# HLK-AX3000-KIT-RJ45.net
KiCad netlist of a schematic drawn in Altium Designer
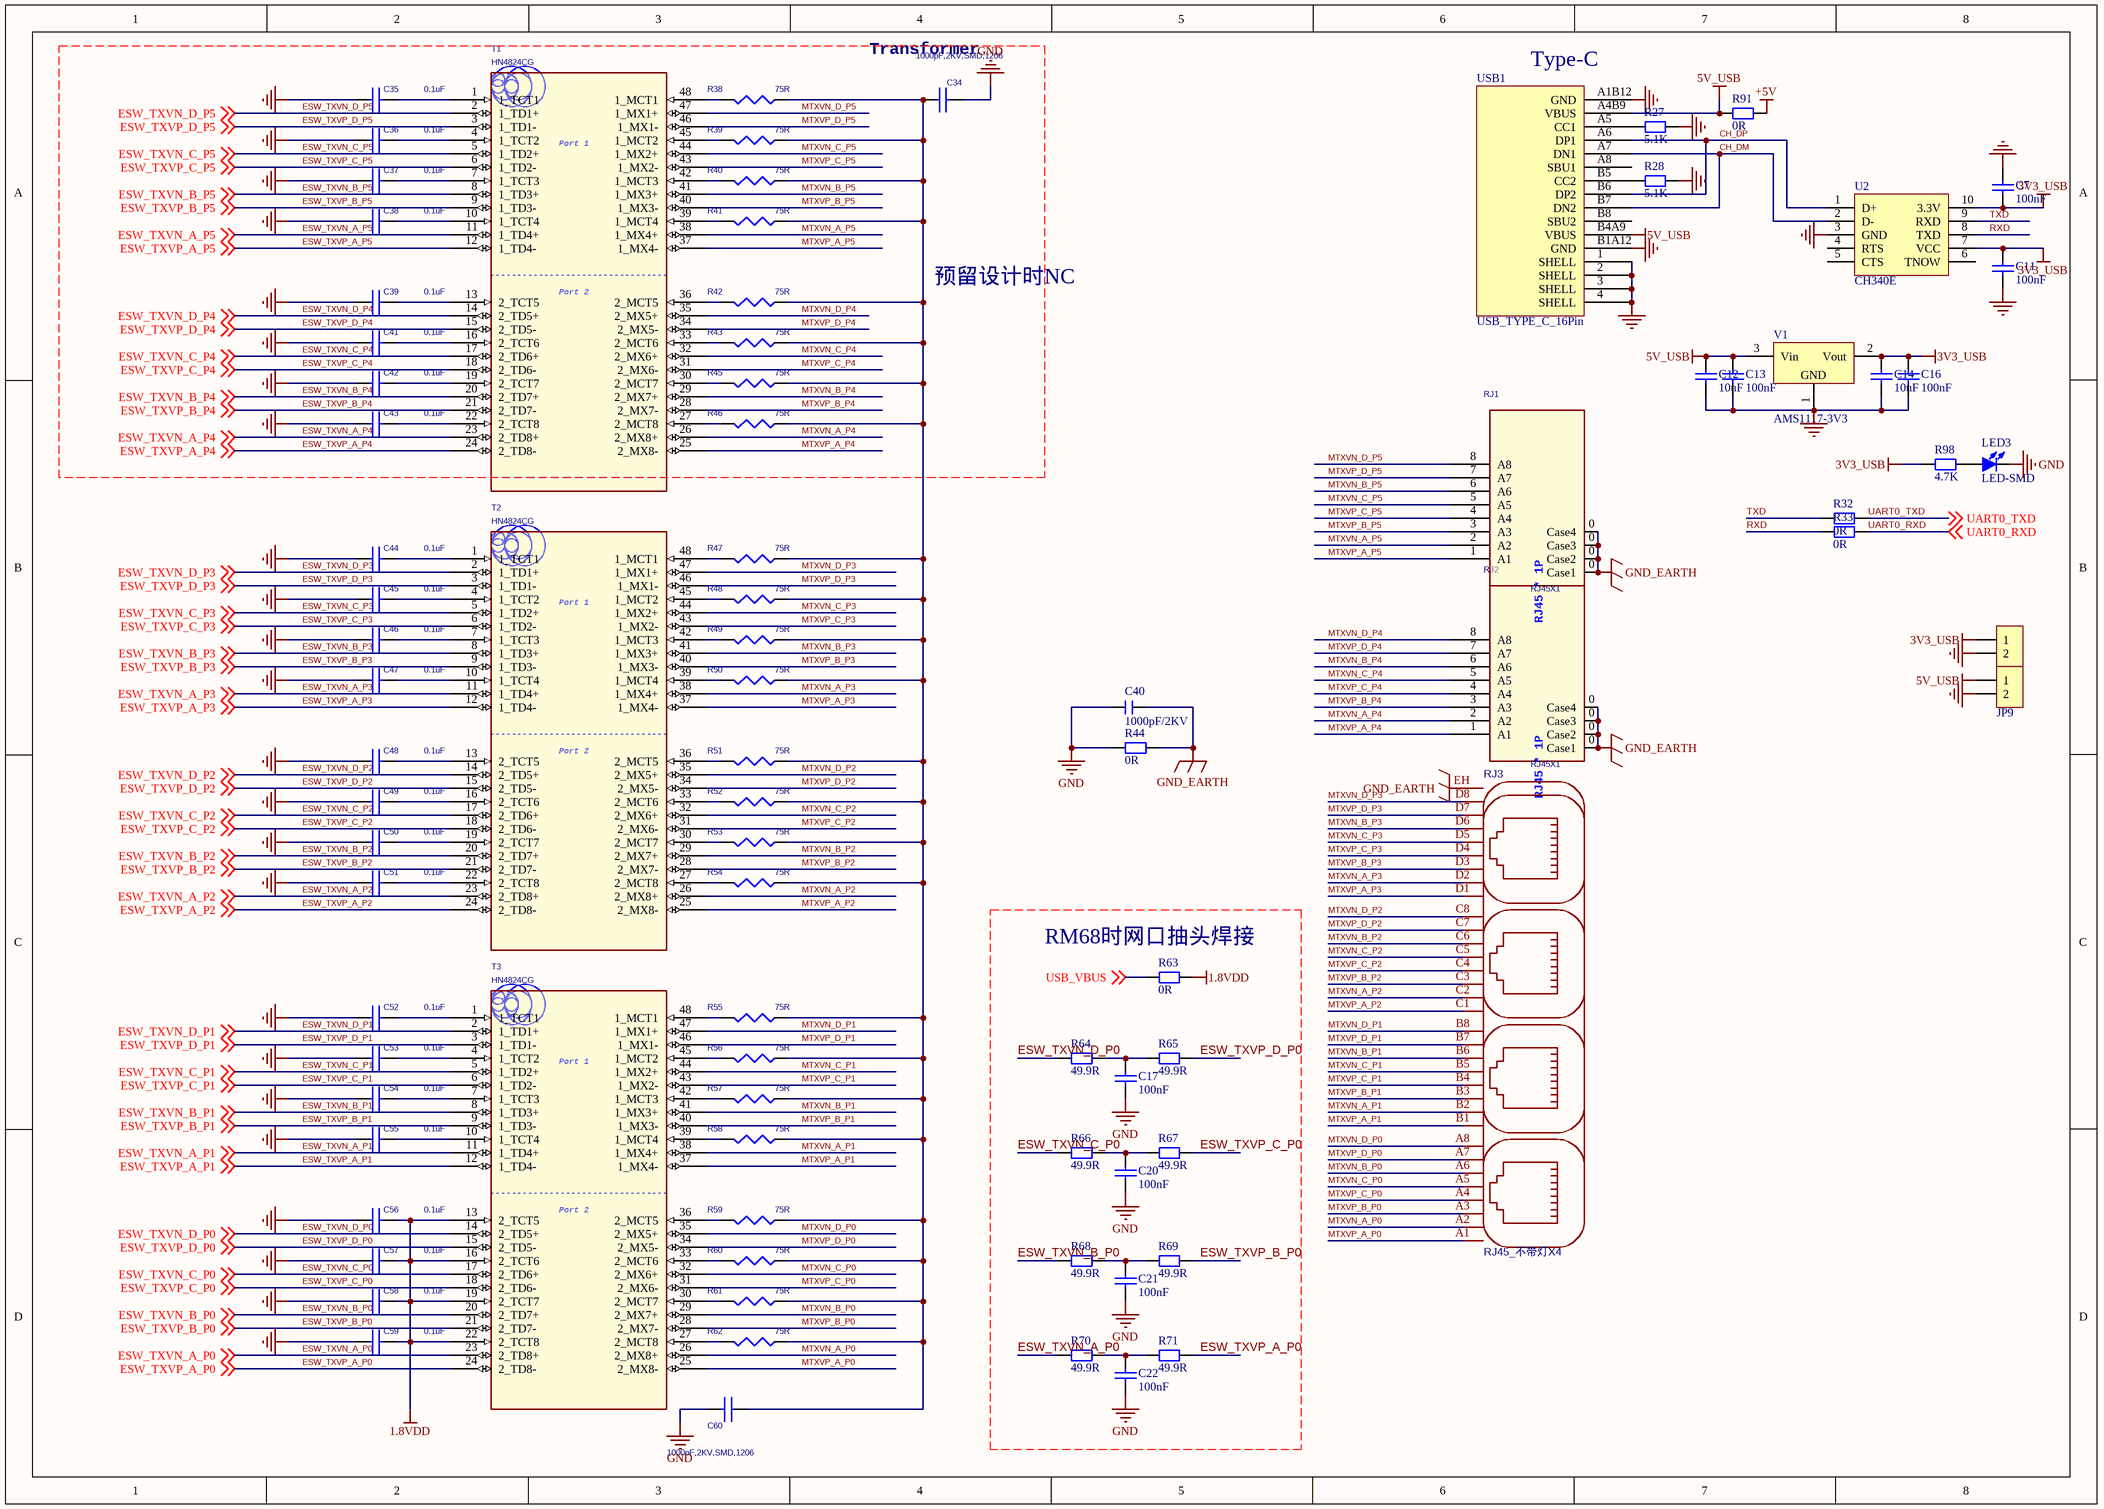
[diagram p0: HLK-AX3000-KIT-RJ45.SchDoc]

(export (version "E")
  (design (tool "Eeschema 10.0.6"))
  (components
    (comp (ref "C7")
      (value "100nF")
      (footprint "C 0402_L")
      (description "Capacitor")
      (libsource (lib "LORATEMPSENSOR_V0.02") (part "Cap"))
    )
    (comp (ref "C11")
      (value "100nF")
      (footprint "C 0402_L")
      (description "Capacitor")
      (libsource (lib "LORATEMPSENSOR_V0.02") (part "Cap"))
    )
    (comp (ref "C12")
      (value "10uF")
      (footprint "C 0603_L")
      (description "Capacitor")
      (fields
        (field (name "MANUFACTURER") "Generic Components")
        (field (name "PUBLISHER") "Altium Hobart Technology Centre")
      )
      (libsource (lib "*") (part "Cap"))
    )
    (comp (ref "C13")
      (value "100nF")
      (footprint "C 0402_L")
      (description "Capacitor")
      (libsource (lib "LORATEMPSENSOR_V0.02") (part "Cap"))
    )
    (comp (ref "C14")
      (value "10uF")
      (footprint "C 0603_L")
      (description "Capacitor")
      (fields
        (field (name "MANUFACTURER") "Generic Components")
        (field (name "PUBLISHER") "Altium Hobart Technology Centre")
      )
      (libsource (lib "*") (part "Cap"))
    )
    (comp (ref "C16")
      (value "100nF")
      (footprint "C 0402_L")
      (description "Capacitor")
      (libsource (lib "LORATEMPSENSOR_V0.02") (part "Cap"))
    )
    (comp (ref "C17")
      (value "100nF")
      (footprint "C 0402_L")
      (description "Capacitor")
      (libsource (lib "LORATEMPSENSOR_V0.02") (part "Cap"))
    )
    (comp (ref "C20")
      (value "100nF")
      (footprint "C 0402_L")
      (description "Capacitor")
      (libsource (lib "LORATEMPSENSOR_V0.02") (part "Cap"))
    )
    (comp (ref "C21")
      (value "100nF")
      (footprint "C 0402_L")
      (description "Capacitor")
      (libsource (lib "LORATEMPSENSOR_V0.02") (part "Cap"))
    )
    (comp (ref "C22")
      (value "100nF")
      (footprint "C 0402_L")
      (description "Capacitor")
      (libsource (lib "LORATEMPSENSOR_V0.02") (part "Cap"))
    )
    (comp (ref "C34")
      (value "1000pF,2KV,SMD,1206")
      (footprint "C 1206_L")
      (description "Cap, HighVolt, SMD 1206, 2KV")
      (fields (field (name "MANUFACTURER") "Arcotromics") (field (name "BY") "Ralink"))
      (libsource (lib "*") (part "CAP NP_Dup1"))
    )
    (comp (ref "C35")
      (value "0.1uF")
      (footprint "C 0402_L")
      (description "Cap, MLCC, 0402, Y5V, 16V")
      (fields
        (field (name "MANUFACTURER") "地穝")
        (field (name "PART NUMBER") "100-110-03400")
        (field (name "BY") "Ralink")
      )
      (libsource (lib "*") (part "0.1UF/25V_+80%-20%_CC_S0603"))
    )
    (comp (ref "C36")
      (value "0.1uF")
      (footprint "C 0402_L")
      (description "Cap, MLCC, 0402, Y5V, 16V")
      (fields
        (field (name "MANUFACTURER") "地穝")
        (field (name "PART NUMBER") "100-110-03400")
        (field (name "BY") "Ralink")
      )
      (libsource (lib "*") (part "0.1UF/25V_+80%-20%_CC_S0603"))
    )
    (comp (ref "C37")
      (value "0.1uF")
      (footprint "C 0402_L")
      (description "Cap, MLCC, 0402, Y5V, 16V")
      (fields
        (field (name "MANUFACTURER") "地穝")
        (field (name "PART NUMBER") "100-110-03400")
        (field (name "BY") "Ralink")
      )
      (libsource (lib "*") (part "0.1UF/25V_+80%-20%_CC_S0603"))
    )
    (comp (ref "C38")
      (value "0.1uF")
      (footprint "C 0402_L")
      (description "Cap, MLCC, 0402, Y5V, 16V")
      (fields
        (field (name "MANUFACTURER") "地穝")
        (field (name "PART NUMBER") "100-110-03400")
        (field (name "BY") "Ralink")
      )
      (libsource (lib "*") (part "0.1UF/25V_+80%-20%_CC_S0603"))
    )
    (comp (ref "C39")
      (value "0.1uF")
      (footprint "C 0402_L")
      (description "Cap, MLCC, 0402, Y5V, 16V")
      (fields
        (field (name "MANUFACTURER") "地穝")
        (field (name "PART NUMBER") "100-110-03400")
        (field (name "BY") "Ralink")
      )
      (libsource (lib "*") (part "0.1UF/25V_+80%-20%_CC_S0603"))
    )
    (comp (ref "C40")
      (value "1000pF/2KV")
      (footprint "C 1206_L")
      (description "无极性贴片电容")
      (fields (field (name "版权归属") "源创客"))
      (libsource (lib "3.1   - 电阻-电容-电感") (part "C"))
    )
    (comp (ref "C41")
      (value "0.1uF")
      (footprint "C 0402_L")
      (description "Cap, MLCC, 0402, Y5V, 16V")
      (fields
        (field (name "MANUFACTURER") "地穝")
        (field (name "PART NUMBER") "100-110-03400")
        (field (name "BY") "Ralink")
      )
      (libsource (lib "*") (part "0.1UF/25V_+80%-20%_CC_S0603"))
    )
    (comp (ref "C42")
      (value "0.1uF")
      (footprint "C 0402_L")
      (description "Cap, MLCC, 0402, Y5V, 16V")
      (fields
        (field (name "MANUFACTURER") "地穝")
        (field (name "PART NUMBER") "100-110-03400")
        (field (name "BY") "Ralink")
      )
      (libsource (lib "*") (part "0.1UF/25V_+80%-20%_CC_S0603"))
    )
    (comp (ref "C43")
      (value "0.1uF")
      (footprint "C 0402_L")
      (description "Cap, MLCC, 0402, Y5V, 16V")
      (fields
        (field (name "MANUFACTURER") "地穝")
        (field (name "PART NUMBER") "100-110-03400")
        (field (name "BY") "Ralink")
      )
      (libsource (lib "*") (part "0.1UF/25V_+80%-20%_CC_S0603"))
    )
    (comp (ref "C44")
      (value "0.1uF")
      (footprint "C 0402_L")
      (description "Cap, MLCC, 0402, Y5V, 16V")
      (fields
        (field (name "PART NUMBER") "100-110-03400")
        (field (name "MANUFACTURER") "地穝")
        (field (name "BY") "Ralink")
      )
      (libsource (lib "*") (part "0.1UF/25V_+80%-20%_CC_S0603"))
    )
    (comp (ref "C45")
      (value "0.1uF")
      (footprint "C 0402_L")
      (description "Cap, MLCC, 0402, Y5V, 16V")
      (fields
        (field (name "PART NUMBER") "100-110-03400")
        (field (name "MANUFACTURER") "地穝")
        (field (name "BY") "Ralink")
      )
      (libsource (lib "*") (part "0.1UF/25V_+80%-20%_CC_S0603"))
    )
    (comp (ref "C46")
      (value "0.1uF")
      (footprint "C 0402_L")
      (description "Cap, MLCC, 0402, Y5V, 16V")
      (fields
        (field (name "PART NUMBER") "100-110-03400")
        (field (name "MANUFACTURER") "地穝")
        (field (name "BY") "Ralink")
      )
      (libsource (lib "*") (part "0.1UF/25V_+80%-20%_CC_S0603"))
    )
    (comp (ref "C47")
      (value "0.1uF")
      (footprint "C 0402_L")
      (description "Cap, MLCC, 0402, Y5V, 16V")
      (fields
        (field (name "PART NUMBER") "100-110-03400")
        (field (name "MANUFACTURER") "地穝")
        (field (name "BY") "Ralink")
      )
      (libsource (lib "*") (part "0.1UF/25V_+80%-20%_CC_S0603"))
    )
    (comp (ref "C48")
      (value "0.1uF")
      (footprint "C 0402_L")
      (description "Cap, MLCC, 0402, Y5V, 16V")
      (fields
        (field (name "MANUFACTURER") "地穝")
        (field (name "PART NUMBER") "100-110-03400")
        (field (name "BY") "Ralink")
      )
      (libsource (lib "*") (part "0.1UF/25V_+80%-20%_CC_S0603"))
    )
    (comp (ref "C49")
      (value "0.1uF")
      (footprint "C 0402_L")
      (description "Cap, MLCC, 0402, Y5V, 16V")
      (fields
        (field (name "MANUFACTURER") "地穝")
        (field (name "PART NUMBER") "100-110-03400")
        (field (name "BY") "Ralink")
      )
      (libsource (lib "*") (part "0.1UF/25V_+80%-20%_CC_S0603"))
    )
    (comp (ref "C50")
      (value "0.1uF")
      (footprint "C 0402_L")
      (description "Cap, MLCC, 0402, Y5V, 16V")
      (fields
        (field (name "MANUFACTURER") "地穝")
        (field (name "PART NUMBER") "100-110-03400")
        (field (name "BY") "Ralink")
      )
      (libsource (lib "*") (part "0.1UF/25V_+80%-20%_CC_S0603"))
    )
    (comp (ref "C51")
      (value "0.1uF")
      (footprint "C 0402_L")
      (description "Cap, MLCC, 0402, Y5V, 16V")
      (fields
        (field (name "MANUFACTURER") "地穝")
        (field (name "PART NUMBER") "100-110-03400")
        (field (name "BY") "Ralink")
      )
      (libsource (lib "*") (part "0.1UF/25V_+80%-20%_CC_S0603"))
    )
    (comp (ref "C52")
      (value "0.1uF")
      (footprint "C 0402_L")
      (description "Cap, MLCC, 0402, Y5V, 16V")
      (fields
        (field (name "MANUFACTURER") "地穝")
        (field (name "PART NUMBER") "100-110-03400")
        (field (name "BY") "Ralink")
      )
      (libsource (lib "*") (part "0.1UF/25V_+80%-20%_CC_S0603"))
    )
    (comp (ref "C53")
      (value "0.1uF")
      (footprint "C 0402_L")
      (description "Cap, MLCC, 0402, Y5V, 16V")
      (fields
        (field (name "MANUFACTURER") "地穝")
        (field (name "PART NUMBER") "100-110-03400")
        (field (name "BY") "Ralink")
      )
      (libsource (lib "*") (part "0.1UF/25V_+80%-20%_CC_S0603"))
    )
    (comp (ref "C54")
      (value "0.1uF")
      (footprint "C 0402_L")
      (description "Cap, MLCC, 0402, Y5V, 16V")
      (fields
        (field (name "PART NUMBER") "100-110-03400")
        (field (name "MANUFACTURER") "地穝")
        (field (name "BY") "Ralink")
      )
      (libsource (lib "*") (part "0.1UF/25V_+80%-20%_CC_S0603"))
    )
    (comp (ref "C55")
      (value "0.1uF")
      (footprint "C 0402_L")
      (description "Cap, MLCC, 0402, Y5V, 16V")
      (fields
        (field (name "PART NUMBER") "100-110-03400")
        (field (name "MANUFACTURER") "地穝")
        (field (name "BY") "Ralink")
      )
      (libsource (lib "*") (part "0.1UF/25V_+80%-20%_CC_S0603"))
    )
    (comp (ref "C56")
      (value "0.1uF")
      (footprint "C 0402_L")
      (description "Cap, MLCC, 0402, Y5V, 16V")
      (fields
        (field (name "MANUFACTURER") "地穝")
        (field (name "PART NUMBER") "100-110-03400")
        (field (name "BY") "Ralink")
      )
      (libsource (lib "*") (part "0.1UF/25V_+80%-20%_CC_S0603"))
    )
    (comp (ref "C57")
      (value "0.1uF")
      (footprint "C 0402_L")
      (description "Cap, MLCC, 0402, Y5V, 16V")
      (fields
        (field (name "MANUFACTURER") "地穝")
        (field (name "PART NUMBER") "100-110-03400")
        (field (name "BY") "Ralink")
      )
      (libsource (lib "*") (part "0.1UF/25V_+80%-20%_CC_S0603"))
    )
    (comp (ref "C58")
      (value "0.1uF")
      (footprint "C 0402_L")
      (description "Cap, MLCC, 0402, Y5V, 16V")
      (fields
        (field (name "PART NUMBER") "100-110-03400")
        (field (name "MANUFACTURER") "地穝")
        (field (name "BY") "Ralink")
      )
      (libsource (lib "*") (part "0.1UF/25V_+80%-20%_CC_S0603"))
    )
    (comp (ref "C59")
      (value "0.1uF")
      (footprint "C 0402_L")
      (description "Cap, MLCC, 0402, Y5V, 16V")
      (fields
        (field (name "PART NUMBER") "100-110-03400")
        (field (name "MANUFACTURER") "地穝")
        (field (name "BY") "Ralink")
      )
      (libsource (lib "*") (part "0.1UF/25V_+80%-20%_CC_S0603"))
    )
    (comp (ref "C60")
      (value "1000pF,2KV,SMD,1206")
      (footprint "C 1206_L")
      (description "Cap, HighVolt, SMD 1206, 2KV")
      (fields (field (name "MANUFACTURER") "Arcotromics") (field (name "BY") "Ralink"))
      (libsource (lib "*") (part "CAP NP_Dup1"))
    )
    (comp (ref "JP8")
      (value "HDR-1X2")
      (footprint "HDR2.54-LI-2P")
      (description "2P接插件")
      (fields (field (name "版权归属") "源创客"))
      (libsource (lib "4.5   - 接插件-脚距2.54") (part "Header 2"))
    )
    (comp (ref "JP9")
      (value "HDR-1X2")
      (footprint "HDR2.54-LI-2P")
      (description "2P接插件")
      (fields (field (name "版权归属") "源创客"))
      (libsource (lib "4.5   - 接插件-脚距2.54") (part "Header 2"))
    )
    (comp (ref "LED3")
      (value "LED-SMD")
      (footprint "LED 0603G-L")
      (description "贴片LED")
      (fields (field (name "版权归属") "源创客"))
      (libsource (lib "9.1   - LED") (part "LED-SMD"))
    )
    (comp (ref "R27")
      (value "5.1K")
      (footprint "R 0402_L")
      (description "贴片电阻")
      (fields (field (name "版权归属") "源创客"))
      (libsource (lib "3.1   - 电阻-电容-电感") (part "R"))
    )
    (comp (ref "R28")
      (value "5.1K")
      (footprint "R 0402_L")
      (description "贴片电阻")
      (fields (field (name "版权归属") "源创客"))
      (libsource (lib "3.1   - 电阻-电容-电感") (part "R"))
    )
    (comp (ref "R32")
      (value "0R")
      (footprint "R 0402_L")
      (description "贴片电阻")
      (fields (field (name "版权归属") "源创客"))
      (libsource (lib "3.1   - 电阻-电容-电感") (part "R"))
    )
    (comp (ref "R33")
      (value "0R")
      (footprint "R 0402_L")
      (description "贴片电阻")
      (fields (field (name "版权归属") "源创客"))
      (libsource (lib "3.1   - 电阻-电容-电感") (part "R"))
    )
    (comp (ref "R38")
      (value "75R")
      (footprint "R 0402_L")
      (description "Resistor, 0402, 5%")
      (fields
        (field (name "MANUFACTURER") "驾м")
        (field (name "PART NUMBER") "110-110-03300")
        (field (name "BY") "Ralink")
      )
      (libsource (lib "*") (part "R75_1%_S0603"))
    )
    (comp (ref "R39")
      (value "75R")
      (footprint "R 0402_L")
      (description "Resistor, 0402, 5%")
      (fields
        (field (name "MANUFACTURER") "驾м")
        (field (name "PART NUMBER") "110-110-03300")
        (field (name "BY") "Ralink")
      )
      (libsource (lib "*") (part "R75_1%_S0603"))
    )
    (comp (ref "R40")
      (value "75R")
      (footprint "R 0402_L")
      (description "Resistor, 0402, 5%")
      (fields
        (field (name "MANUFACTURER") "驾м")
        (field (name "PART NUMBER") "110-110-03300")
        (field (name "BY") "Ralink")
      )
      (libsource (lib "*") (part "R75_1%_S0603"))
    )
    (comp (ref "R41")
      (value "75R")
      (footprint "R 0402_L")
      (description "Resistor, 0402, 5%")
      (fields
        (field (name "PART NUMBER") "110-110-03300")
        (field (name "MANUFACTURER") "驾м")
        (field (name "BY") "Ralink")
      )
      (libsource (lib "*") (part "R75_1%_S0603"))
    )
    (comp (ref "R42")
      (value "75R")
      (footprint "R 0402_L")
      (description "Resistor, 0402, 5%")
      (fields
        (field (name "MANUFACTURER") "驾м")
        (field (name "PART NUMBER") "110-110-03300")
        (field (name "BY") "Ralink")
      )
      (libsource (lib "*") (part "R75_1%_S0603"))
    )
    (comp (ref "R43")
      (value "75R")
      (footprint "R 0402_L")
      (description "Resistor, 0402, 5%")
      (fields
        (field (name "MANUFACTURER") "驾м")
        (field (name "PART NUMBER") "110-110-03300")
        (field (name "BY") "Ralink")
      )
      (libsource (lib "*") (part "R75_1%_S0603"))
    )
    (comp (ref "R44")
      (value "0R")
      (footprint "R 1206_L")
      (description "贴片电阻")
      (fields (field (name "版权归属") "源创客"))
      (libsource (lib "3.1   - 电阻-电容-电感") (part "R"))
    )
    (comp (ref "R45")
      (value "75R")
      (footprint "R 0402_L")
      (description "Resistor, 0402, 5%")
      (fields
        (field (name "MANUFACTURER") "驾м")
        (field (name "PART NUMBER") "110-110-03300")
        (field (name "BY") "Ralink")
      )
      (libsource (lib "*") (part "R75_1%_S0603"))
    )
    (comp (ref "R46")
      (value "75R")
      (footprint "R 0402_L")
      (description "Resistor, 0402, 5%")
      (fields
        (field (name "PART NUMBER") "110-110-03300")
        (field (name "MANUFACTURER") "驾м")
        (field (name "BY") "Ralink")
      )
      (libsource (lib "*") (part "R75_1%_S0603"))
    )
    (comp (ref "R47")
      (value "75R")
      (footprint "R 0402_L")
      (description "Resistor, SMD 0402, 5%")
      (fields
        (field (name "MANUFACTURER") "驾м")
        (field (name "PART NUMBER") "110-110-03300")
        (field (name "BY") "Ralink")
      )
      (libsource (lib "*") (part "R75_1%_S0603"))
    )
    (comp (ref "R48")
      (value "75R")
      (footprint "R 0402_L")
      (description "Resistor, SMD 0402, 5%")
      (fields
        (field (name "PART NUMBER") "110-110-03300")
        (field (name "MANUFACTURER") "驾м")
        (field (name "BY") "Ralink")
      )
      (libsource (lib "*") (part "R75_1%_S0603"))
    )
    (comp (ref "R49")
      (value "75R")
      (footprint "R 0402_L")
      (description "Resistor, SMD 0402, 5%")
      (fields
        (field (name "PART NUMBER") "110-110-03300")
        (field (name "MANUFACTURER") "驾м")
        (field (name "BY") "Ralink")
      )
      (libsource (lib "*") (part "R75_1%_S0603"))
    )
    (comp (ref "R50")
      (value "75R")
      (footprint "R 0402_L")
      (description "Resistor, SMD 0402, 5%")
      (fields
        (field (name "MANUFACTURER") "驾м")
        (field (name "PART NUMBER") "110-110-03300")
        (field (name "BY") "Ralink")
      )
      (libsource (lib "*") (part "R75_1%_S0603"))
    )
    (comp (ref "R51")
      (value "75R")
      (footprint "R 0402_L")
      (description "Resistor, SMD 0402, 5%")
      (fields
        (field (name "PART NUMBER") "110-110-03300")
        (field (name "MANUFACTURER") "驾м")
        (field (name "BY") "Ralink")
      )
      (libsource (lib "*") (part "R75_1%_S0603"))
    )
    (comp (ref "R52")
      (value "75R")
      (footprint "R 0402_L")
      (description "Resistor, SMD 0402, 5%")
      (fields
        (field (name "PART NUMBER") "110-110-03300")
        (field (name "MANUFACTURER") "驾м")
        (field (name "BY") "Ralink")
      )
      (libsource (lib "*") (part "R75_1%_S0603"))
    )
    (comp (ref "R53")
      (value "75R")
      (footprint "R 0402_L")
      (description "Resistor, SMD 0402, 5%")
      (fields
        (field (name "MANUFACTURER") "驾м")
        (field (name "PART NUMBER") "110-110-03300")
        (field (name "BY") "Ralink")
      )
      (libsource (lib "*") (part "R75_1%_S0603"))
    )
    (comp (ref "R54")
      (value "75R")
      (footprint "R 0402_L")
      (description "Resistor, SMD 0402, 5%")
      (fields
        (field (name "PART NUMBER") "110-110-03300")
        (field (name "MANUFACTURER") "驾м")
        (field (name "BY") "Ralink")
      )
      (libsource (lib "*") (part "R75_1%_S0603"))
    )
    (comp (ref "R55")
      (value "75R")
      (footprint "R 0402_L")
      (description "Resistor, SMD 0402, 5%")
      (fields
        (field (name "PART NUMBER") "110-110-03300")
        (field (name "MANUFACTURER") "驾м")
        (field (name "BY") "Ralink")
      )
      (libsource (lib "*") (part "R75_1%_S0603"))
    )
    (comp (ref "R56")
      (value "75R")
      (footprint "R 0402_L")
      (description "Resistor, SMD 0402, 5%")
      (fields
        (field (name "PART NUMBER") "110-110-03300")
        (field (name "MANUFACTURER") "驾м")
        (field (name "BY") "Ralink")
      )
      (libsource (lib "*") (part "R75_1%_S0603"))
    )
    (comp (ref "R57")
      (value "75R")
      (footprint "R 0402_L")
      (description "Resistor, SMD 0402, 5%")
      (fields
        (field (name "PART NUMBER") "110-110-03300")
        (field (name "MANUFACTURER") "驾м")
        (field (name "BY") "Ralink")
      )
      (libsource (lib "*") (part "R75_1%_S0603"))
    )
    (comp (ref "R58")
      (value "75R")
      (footprint "R 0402_L")
      (description "Resistor, SMD 0402, 5%")
      (fields
        (field (name "MANUFACTURER") "驾м")
        (field (name "PART NUMBER") "110-110-03300")
        (field (name "BY") "Ralink")
      )
      (libsource (lib "*") (part "R75_1%_S0603"))
    )
    (comp (ref "R59")
      (value "75R")
      (footprint "R 0402_L")
      (description "Resistor, SMD 0402, 5%")
      (fields
        (field (name "MANUFACTURER") "驾м")
        (field (name "PART NUMBER") "110-110-03300")
        (field (name "BY") "Ralink")
      )
      (libsource (lib "*") (part "R75_1%_S0603"))
    )
    (comp (ref "R60")
      (value "75R")
      (footprint "R 0402_L")
      (description "Resistor, SMD 0402, 5%")
      (fields
        (field (name "MANUFACTURER") "驾м")
        (field (name "PART NUMBER") "110-110-03300")
        (field (name "BY") "Ralink")
      )
      (libsource (lib "*") (part "R75_1%_S0603"))
    )
    (comp (ref "R61")
      (value "75R")
      (footprint "R 0402_L")
      (description "Resistor, SMD 0402, 5%")
      (fields
        (field (name "PART NUMBER") "110-110-03300")
        (field (name "MANUFACTURER") "驾м")
        (field (name "BY") "Ralink")
      )
      (libsource (lib "*") (part "R75_1%_S0603"))
    )
    (comp (ref "R62")
      (value "75R")
      (footprint "R 0402_L")
      (description "Resistor, SMD 0402, 5%")
      (fields
        (field (name "MANUFACTURER") "驾м")
        (field (name "PART NUMBER") "110-110-03300")
        (field (name "BY") "Ralink")
      )
      (libsource (lib "*") (part "R75_1%_S0603"))
    )
    (comp (ref "R63")
      (value "0R")
      (footprint "R 0402_L")
      (description "贴片电阻")
      (fields (field (name "版权归属") "源创客"))
      (libsource (lib "3.1   - 电阻-电容-电感") (part "R"))
    )
    (comp (ref "R64")
      (value "49.9R")
      (footprint "R 0402_L")
      (description "贴片电阻")
      (fields (field (name "版权归属") "源创客"))
      (libsource (lib "3.1   - 电阻-电容-电感") (part "R"))
    )
    (comp (ref "R65")
      (value "49.9R")
      (footprint "R 0402_L")
      (description "贴片电阻")
      (fields (field (name "版权归属") "源创客"))
      (libsource (lib "3.1   - 电阻-电容-电感") (part "R"))
    )
    (comp (ref "R66")
      (value "49.9R")
      (footprint "R 0402_L")
      (description "贴片电阻")
      (fields (field (name "版权归属") "源创客"))
      (libsource (lib "3.1   - 电阻-电容-电感") (part "R"))
    )
    (comp (ref "R67")
      (value "49.9R")
      (footprint "R 0402_L")
      (description "贴片电阻")
      (fields (field (name "版权归属") "源创客"))
      (libsource (lib "3.1   - 电阻-电容-电感") (part "R"))
    )
    (comp (ref "R68")
      (value "49.9R")
      (footprint "R 0402_L")
      (description "贴片电阻")
      (fields (field (name "版权归属") "源创客"))
      (libsource (lib "3.1   - 电阻-电容-电感") (part "R"))
    )
    (comp (ref "R69")
      (value "49.9R")
      (footprint "R 0402_L")
      (description "贴片电阻")
      (fields (field (name "版权归属") "源创客"))
      (libsource (lib "3.1   - 电阻-电容-电感") (part "R"))
    )
    (comp (ref "R70")
      (value "49.9R")
      (footprint "R 0402_L")
      (description "贴片电阻")
      (fields (field (name "版权归属") "源创客"))
      (libsource (lib "3.1   - 电阻-电容-电感") (part "R"))
    )
    (comp (ref "R71")
      (value "49.9R")
      (footprint "R 0402_L")
      (description "贴片电阻")
      (fields (field (name "版权归属") "源创客"))
      (libsource (lib "3.1   - 电阻-电容-电感") (part "R"))
    )
    (comp (ref "R91")
      (value "0R")
      (footprint "R 0603_L")
      (description "贴片电阻")
      (fields (field (name "版权归属") "源创客"))
      (libsource (lib "3.1   - 电阻-电容-电感") (part "R"))
    )
    (comp (ref "R98")
      (value "4.7K")
      (footprint "R 0402_L")
      (description "贴片电阻")
      (fields (field (name "版权归属") "源创客"))
      (libsource (lib "3.1   - 电阻-电容-电感") (part "R"))
    )
    (comp (ref "RJ1")
      (value "RJ45X1")
      (footprint "RJ45_网口不带灯X1")
      (fields
        (field (name "MANUFACTURER") "救┹")
        (field (name "MANUFACTURER'S PART NUMBER") "PJ-A1-BXBH-FDNNN-1")
        (field (name "PART NUMBER") "214411*12311105")
      )
      (libsource (lib "*") (part "RJ45X1_4"))
    )
    (comp (ref "RJ2")
      (value "RJ45X1")
      (footprint "RJ45_网口不带灯X1")
      (fields
        (field (name "MANUFACTURER") "救┹")
        (field (name "MANUFACTURER'S PART NUMBER") "PJ-A1-BXBH-FDNNN-1")
        (field (name "PART NUMBER") "214411*12311105")
      )
      (libsource (lib "*") (part "RJ45X1_4"))
    )
    (comp (ref "RJ3")
      (value "RJ45_不带灯X4")
      (footprint "RJ45_网口不带灯X4")
      (fields
        (field (name "BOM_SUPPLIER PART") "C77852")
        (field (name "BOM_MANUFACTURER PART") "DS1129-02-S80BP")
        (field (name "SUBPART_NO") "3")
      )
      (libsource (lib "MY SCHLIB") (part "RJ45_不带灯X4"))
    )
    (comp (ref "T1")
      (value "HN4824CG")
      (footprint "TRANSFORMER/48P/SMD/GS5014LF")
      (libsource (lib "*") (part "XMER 2P G2PM109N"))
    )
    (comp (ref "T2")
      (value "HN4824CG")
      (footprint "TRANSFORMER/48P/SMD/GS5014LF")
      (libsource (lib "*") (part "XMER 2P G2PM109N"))
    )
    (comp (ref "T3")
      (value "HN4824CG")
      (footprint "TRANSFORMER/48P/SMD/GS5014LF")
      (libsource (lib "*") (part "XMER 2P G2PM109N"))
    )
    (comp (ref "U2")
      (value "CH340E")
      (footprint "MSOP10_L")
      (description "串口芯片")
      (libsource (lib "1.1   - IC芯片") (part "CH340E"))
    )
    (comp (ref "USB1")
      (value "USB_TYPE_C_16Pin")
      (footprint "USB-C-16PIN-1")
      (libsource (lib "Interface") (part "USB_TYPE_C_16Pin"))
    )
    (comp (ref "V1")
      (value "AMS1117-3V3")
      (footprint "SOT223_L")
      (description "三端稳压芯片")
      (fields (field (name "版权归属") "源创客"))
      (libsource (lib "1.3   - 电源类芯片") (part "AMS1117"))
    )
  )
  (nets
    (net (code "1") (name "+5V") (class "Default")
      (node (ref "R91") (pin "2") (pinfunction "2_2") (pintype "passive"))
    )
    (net (code "2") (name "/CH_DM") (class "Default")
      (node (ref "U2") (pin "2") (pinfunction "D-_2") (pintype "passive"))
      (node (ref "USB1") (pin "A7") (pinfunction "DN1_A7") (pintype "passive"))
      (node (ref "USB1") (pin "B7") (pinfunction "DN2_B7") (pintype "passive"))
    )
    (net (code "3") (name "/CH_DP") (class "Default")
      (node (ref "U2") (pin "1") (pinfunction "D+_1") (pintype "passive"))
      (node (ref "USB1") (pin "A6") (pinfunction "DP1_A6") (pintype "passive"))
      (node (ref "USB1") (pin "B6") (pinfunction "DP2_B6") (pintype "passive"))
    )
    (net (code "4") (name "/MTXVN_A_P0") (class "Default")
      (node (ref "RJ3") (pin "A2") (pinfunction "A2_A2") (pintype "passive"))
      (node (ref "T3") (pin "26") (pinfunction "2_MX8+_26") (pintype "bidirectional"))
    )
    (net (code "5") (name "/MTXVN_A_P1") (class "Default")
      (node (ref "RJ3") (pin "B2") (pinfunction "B2_B2") (pintype "passive"))
      (node (ref "T3") (pin "38") (pinfunction "1_MX4+_38") (pintype "bidirectional"))
    )
    (net (code "6") (name "/MTXVN_A_P2") (class "Default")
      (node (ref "RJ3") (pin "C2") (pinfunction "C2_C2") (pintype "passive"))
      (node (ref "T2") (pin "26") (pinfunction "2_MX8+_26") (pintype "bidirectional"))
    )
    (net (code "7") (name "/MTXVN_A_P3") (class "Default")
      (node (ref "RJ3") (pin "D2") (pinfunction "D2_D2") (pintype "passive"))
      (node (ref "T2") (pin "38") (pinfunction "1_MX4+_38") (pintype "bidirectional"))
    )
    (net (code "8") (name "/MTXVN_A_P4") (class "Default")
      (node (ref "RJ2") (pin "2") (pinfunction "A2_2") (pintype "passive"))
      (node (ref "T1") (pin "26") (pinfunction "2_MX8+_26") (pintype "bidirectional"))
    )
    (net (code "9") (name "/MTXVN_A_P5") (class "Default")
      (node (ref "RJ1") (pin "2") (pinfunction "A2_2") (pintype "passive"))
      (node (ref "T1") (pin "38") (pinfunction "1_MX4+_38") (pintype "bidirectional"))
    )
    (net (code "10") (name "/MTXVN_B_P0") (class "Default")
      (node (ref "RJ3") (pin "A6") (pinfunction "A6_A6") (pintype "passive"))
      (node (ref "T3") (pin "29") (pinfunction "2_MX7+_29") (pintype "bidirectional"))
    )
    (net (code "11") (name "/MTXVN_B_P1") (class "Default")
      (node (ref "RJ3") (pin "B6") (pinfunction "B6_B6") (pintype "passive"))
      (node (ref "T3") (pin "41") (pinfunction "1_MX3+_41") (pintype "bidirectional"))
    )
    (net (code "12") (name "/MTXVN_B_P2") (class "Default")
      (node (ref "RJ3") (pin "C6") (pinfunction "C6_C6") (pintype "passive"))
      (node (ref "T2") (pin "29") (pinfunction "2_MX7+_29") (pintype "bidirectional"))
    )
    (net (code "13") (name "/MTXVN_B_P3") (class "Default")
      (node (ref "RJ3") (pin "D6") (pinfunction "D6_D6") (pintype "passive"))
      (node (ref "T2") (pin "41") (pinfunction "1_MX3+_41") (pintype "bidirectional"))
    )
    (net (code "14") (name "/MTXVN_B_P4") (class "Default")
      (node (ref "RJ2") (pin "6") (pinfunction "A6_6") (pintype "passive"))
      (node (ref "T1") (pin "29") (pinfunction "2_MX7+_29") (pintype "bidirectional"))
    )
    (net (code "15") (name "/MTXVN_B_P5") (class "Default")
      (node (ref "RJ1") (pin "6") (pinfunction "A6_6") (pintype "passive"))
      (node (ref "T1") (pin "41") (pinfunction "1_MX3+_41") (pintype "bidirectional"))
    )
    (net (code "16") (name "/MTXVN_C_P0") (class "Default")
      (node (ref "RJ3") (pin "A5") (pinfunction "A5_A5") (pintype "passive"))
      (node (ref "T3") (pin "32") (pinfunction "2_MX6+_32") (pintype "bidirectional"))
    )
    (net (code "17") (name "/MTXVN_C_P1") (class "Default")
      (node (ref "RJ3") (pin "B5") (pinfunction "B5_B5") (pintype "passive"))
      (node (ref "T3") (pin "44") (pinfunction "1_MX2+_44") (pintype "bidirectional"))
    )
    (net (code "18") (name "/MTXVN_C_P2") (class "Default")
      (node (ref "RJ3") (pin "C5") (pinfunction "C5_C5") (pintype "passive"))
      (node (ref "T2") (pin "32") (pinfunction "2_MX6+_32") (pintype "bidirectional"))
    )
    (net (code "19") (name "/MTXVN_C_P3") (class "Default")
      (node (ref "RJ3") (pin "D5") (pinfunction "D5_D5") (pintype "passive"))
      (node (ref "T2") (pin "44") (pinfunction "1_MX2+_44") (pintype "bidirectional"))
    )
    (net (code "20") (name "/MTXVN_C_P4") (class "Default")
      (node (ref "RJ2") (pin "5") (pinfunction "A5_5") (pintype "passive"))
      (node (ref "T1") (pin "32") (pinfunction "2_MX6+_32") (pintype "bidirectional"))
    )
    (net (code "21") (name "/MTXVN_C_P5") (class "Default")
      (node (ref "RJ1") (pin "5") (pinfunction "A5_5") (pintype "passive"))
      (node (ref "T1") (pin "44") (pinfunction "1_MX2+_44") (pintype "bidirectional"))
    )
    (net (code "22") (name "/MTXVN_D_P0") (class "Default")
      (node (ref "RJ3") (pin "A8") (pinfunction "A8_A8") (pintype "passive"))
      (node (ref "T3") (pin "35") (pinfunction "2_MX5+_35") (pintype "bidirectional"))
    )
    (net (code "23") (name "/MTXVN_D_P1") (class "Default")
      (node (ref "RJ3") (pin "B8") (pinfunction "B8_B8") (pintype "passive"))
      (node (ref "T3") (pin "47") (pinfunction "1_MX1+_47") (pintype "bidirectional"))
    )
    (net (code "24") (name "/MTXVN_D_P2") (class "Default")
      (node (ref "RJ3") (pin "C8") (pinfunction "C8_C8") (pintype "passive"))
      (node (ref "T2") (pin "35") (pinfunction "2_MX5+_35") (pintype "bidirectional"))
    )
    (net (code "25") (name "/MTXVN_D_P3") (class "Default")
      (node (ref "RJ3") (pin "D8") (pinfunction "D8_D8") (pintype "passive"))
      (node (ref "T2") (pin "47") (pinfunction "1_MX1+_47") (pintype "bidirectional"))
    )
    (net (code "26") (name "/MTXVN_D_P4") (class "Default")
      (node (ref "RJ2") (pin "8") (pinfunction "A8_8") (pintype "passive"))
      (node (ref "T1") (pin "35") (pinfunction "2_MX5+_35") (pintype "bidirectional"))
    )
    (net (code "27") (name "/MTXVN_D_P5") (class "Default")
      (node (ref "RJ1") (pin "8") (pinfunction "A8_8") (pintype "passive"))
      (node (ref "T1") (pin "47") (pinfunction "1_MX1+_47") (pintype "bidirectional"))
    )
    (net (code "28") (name "/MTXVP_A_P0") (class "Default")
      (node (ref "RJ3") (pin "A1") (pinfunction "A1_A1") (pintype "passive"))
      (node (ref "T3") (pin "25") (pinfunction "2_MX8-_25") (pintype "bidirectional"))
    )
    (net (code "29") (name "/MTXVP_A_P1") (class "Default")
      (node (ref "RJ3") (pin "B1") (pinfunction "B1_B1") (pintype "passive"))
      (node (ref "T3") (pin "37") (pinfunction "1_MX4-_37") (pintype "bidirectional"))
    )
    (net (code "30") (name "/MTXVP_A_P2") (class "Default")
      (node (ref "RJ3") (pin "C1") (pinfunction "C1_C1") (pintype "passive"))
      (node (ref "T2") (pin "25") (pinfunction "2_MX8-_25") (pintype "bidirectional"))
    )
    (net (code "31") (name "/MTXVP_A_P3") (class "Default")
      (node (ref "RJ3") (pin "D1") (pinfunction "D1_D1") (pintype "passive"))
      (node (ref "T2") (pin "37") (pinfunction "1_MX4-_37") (pintype "bidirectional"))
    )
    (net (code "32") (name "/MTXVP_A_P4") (class "Default")
      (node (ref "RJ2") (pin "1") (pinfunction "A1_1") (pintype "passive"))
      (node (ref "T1") (pin "25") (pinfunction "2_MX8-_25") (pintype "bidirectional"))
    )
    (net (code "33") (name "/MTXVP_A_P5") (class "Default")
      (node (ref "RJ1") (pin "1") (pinfunction "A1_1") (pintype "passive"))
      (node (ref "T1") (pin "37") (pinfunction "1_MX4-_37") (pintype "bidirectional"))
    )
    (net (code "34") (name "/MTXVP_B_P0") (class "Default")
      (node (ref "RJ3") (pin "A3") (pinfunction "A3_A3") (pintype "passive"))
      (node (ref "T3") (pin "28") (pinfunction "2_MX7-_28") (pintype "bidirectional"))
    )
    (net (code "35") (name "/MTXVP_B_P1") (class "Default")
      (node (ref "RJ3") (pin "B3") (pinfunction "B3_B3") (pintype "passive"))
      (node (ref "T3") (pin "40") (pinfunction "1_MX3-_40") (pintype "bidirectional"))
    )
    (net (code "36") (name "/MTXVP_B_P2") (class "Default")
      (node (ref "RJ3") (pin "C3") (pinfunction "C3_C3") (pintype "passive"))
      (node (ref "T2") (pin "28") (pinfunction "2_MX7-_28") (pintype "bidirectional"))
    )
    (net (code "37") (name "/MTXVP_B_P3") (class "Default")
      (node (ref "RJ3") (pin "D3") (pinfunction "D3_D3") (pintype "passive"))
      (node (ref "T2") (pin "40") (pinfunction "1_MX3-_40") (pintype "bidirectional"))
    )
    (net (code "38") (name "/MTXVP_B_P4") (class "Default")
      (node (ref "RJ2") (pin "3") (pinfunction "A3_3") (pintype "passive"))
      (node (ref "T1") (pin "28") (pinfunction "2_MX7-_28") (pintype "bidirectional"))
    )
    (net (code "39") (name "/MTXVP_B_P5") (class "Default")
      (node (ref "RJ1") (pin "3") (pinfunction "A3_3") (pintype "passive"))
      (node (ref "T1") (pin "40") (pinfunction "1_MX3-_40") (pintype "bidirectional"))
    )
    (net (code "40") (name "/MTXVP_C_P0") (class "Default")
      (node (ref "RJ3") (pin "A4") (pinfunction "A4_A4") (pintype "passive"))
      (node (ref "T3") (pin "31") (pinfunction "2_MX6-_31") (pintype "bidirectional"))
    )
    (net (code "41") (name "/MTXVP_C_P1") (class "Default")
      (node (ref "RJ3") (pin "B4") (pinfunction "B4_B4") (pintype "passive"))
      (node (ref "T3") (pin "43") (pinfunction "1_MX2-_43") (pintype "bidirectional"))
    )
    (net (code "42") (name "/MTXVP_C_P2") (class "Default")
      (node (ref "RJ3") (pin "C4") (pinfunction "C4_C4") (pintype "passive"))
      (node (ref "T2") (pin "31") (pinfunction "2_MX6-_31") (pintype "bidirectional"))
    )
    (net (code "43") (name "/MTXVP_C_P3") (class "Default")
      (node (ref "RJ3") (pin "D4") (pinfunction "D4_D4") (pintype "passive"))
      (node (ref "T2") (pin "43") (pinfunction "1_MX2-_43") (pintype "bidirectional"))
    )
    (net (code "44") (name "/MTXVP_C_P4") (class "Default")
      (node (ref "RJ2") (pin "4") (pinfunction "A4_4") (pintype "passive"))
      (node (ref "T1") (pin "31") (pinfunction "2_MX6-_31") (pintype "bidirectional"))
    )
    (net (code "45") (name "/MTXVP_C_P5") (class "Default")
      (node (ref "RJ1") (pin "4") (pinfunction "A4_4") (pintype "passive"))
      (node (ref "T1") (pin "43") (pinfunction "1_MX2-_43") (pintype "bidirectional"))
    )
    (net (code "46") (name "/MTXVP_D_P0") (class "Default")
      (node (ref "RJ3") (pin "A7") (pinfunction "A7_A7") (pintype "passive"))
      (node (ref "T3") (pin "34") (pinfunction "2_MX5-_34") (pintype "bidirectional"))
    )
    (net (code "47") (name "/MTXVP_D_P1") (class "Default")
      (node (ref "RJ3") (pin "B7") (pinfunction "B7_B7") (pintype "passive"))
      (node (ref "T3") (pin "46") (pinfunction "1_MX1-_46") (pintype "bidirectional"))
    )
    (net (code "48") (name "/MTXVP_D_P2") (class "Default")
      (node (ref "RJ3") (pin "C7") (pinfunction "C7_C7") (pintype "passive"))
      (node (ref "T2") (pin "34") (pinfunction "2_MX5-_34") (pintype "bidirectional"))
    )
    (net (code "49") (name "/MTXVP_D_P3") (class "Default")
      (node (ref "RJ3") (pin "D7") (pinfunction "D7_D7") (pintype "passive"))
      (node (ref "T2") (pin "46") (pinfunction "1_MX1-_46") (pintype "bidirectional"))
    )
    (net (code "50") (name "/MTXVP_D_P4") (class "Default")
      (node (ref "RJ2") (pin "7") (pinfunction "A7_7") (pintype "passive"))
      (node (ref "T1") (pin "34") (pinfunction "2_MX5-_34") (pintype "bidirectional"))
    )
    (net (code "51") (name "/MTXVP_D_P5") (class "Default")
      (node (ref "RJ1") (pin "7") (pinfunction "A7_7") (pintype "passive"))
      (node (ref "T1") (pin "46") (pinfunction "1_MX1-_46") (pintype "bidirectional"))
    )
    (net (code "52") (name "/RXD") (class "Default")
      (node (ref "R33") (pin "2") (pinfunction "2_2") (pintype "passive"))
      (node (ref "U2") (pin "8") (pinfunction "TXD_8") (pintype "passive"))
    )
    (net (code "53") (name "/TXD") (class "Default")
      (node (ref "R32") (pin "2") (pinfunction "2_2") (pintype "passive"))
      (node (ref "U2") (pin "9") (pinfunction "RXD_9") (pintype "passive"))
    )
    (net (code "54") (name "1.8VDD") (class "Default")
      (node (ref "C56") (pin "2") (pinfunction "2_2") (pintype "passive"))
      (node (ref "C57") (pin "2") (pinfunction "2_2") (pintype "passive"))
      (node (ref "C58") (pin "2") (pinfunction "2_2") (pintype "passive"))
      (node (ref "C59") (pin "2") (pinfunction "2_2") (pintype "passive"))
      (node (ref "R63") (pin "1") (pinfunction "1_1") (pintype "passive"))
      (node (ref "T3") (pin "13") (pinfunction "2_TCT5_13") (pintype "input"))
      (node (ref "T3") (pin "16") (pinfunction "2_TCT6_16") (pintype "input"))
      (node (ref "T3") (pin "19") (pinfunction "2_TCT7_19") (pintype "input"))
      (node (ref "T3") (pin "22") (pinfunction "2_TCT8_22") (pintype "input"))
    )
    (net (code "55") (name "3V3_USB") (class "Default")
      (node (ref "C11") (pin "2") (pinfunction "2_2") (pintype "passive"))
      (node (ref "C14") (pin "2") (pinfunction "2_2") (pintype "passive"))
      (node (ref "C16") (pin "1") (pinfunction "1_1") (pintype "passive"))
      (node (ref "C7") (pin "2") (pinfunction "2_2") (pintype "passive"))
      (node (ref "JP8") (pin "1") (pinfunction "1_1") (pintype "passive"))
      (node (ref "R98") (pin "2") (pinfunction "2_2") (pintype "passive"))
      (node (ref "U2") (pin "10") (pinfunction "3.3V_10") (pintype "passive"))
      (node (ref "U2") (pin "7") (pinfunction "VCC_7") (pintype "passive"))
      (node (ref "V1") (pin "2") (pinfunction "Vout_2") (pintype "passive"))
    )
    (net (code "56") (name "5V_USB") (class "Default")
      (node (ref "C12") (pin "2") (pinfunction "2_2") (pintype "passive"))
      (node (ref "C13") (pin "1") (pinfunction "1_1") (pintype "passive"))
      (node (ref "JP9") (pin "1") (pinfunction "1_1") (pintype "passive"))
      (node (ref "R91") (pin "1") (pinfunction "1_1") (pintype "passive"))
      (node (ref "USB1") (pin "A4B9") (pinfunction "VBUS_A4B9") (pintype "passive"))
      (node (ref "USB1") (pin "B4A9") (pinfunction "VBUS_B4A9") (pintype "passive"))
      (node (ref "V1") (pin "3") (pinfunction "Vin_3") (pintype "passive"))
    )
    (net (code "57") (name "ESW_TXVN_A_P0") (class "Default")
      (node (ref "R70") (pin "1") (pinfunction "1_1") (pintype "passive"))
      (node (ref "T3") (pin "23") (pinfunction "2_TD8+_23") (pintype "bidirectional"))
    )
    (net (code "58") (name "ESW_TXVN_A_P1") (class "Default")
      (node (ref "T3") (pin "11") (pinfunction "1_TD4+_11") (pintype "bidirectional"))
    )
    (net (code "59") (name "ESW_TXVN_A_P2") (class "Default")
      (node (ref "T2") (pin "23") (pinfunction "2_TD8+_23") (pintype "bidirectional"))
    )
    (net (code "60") (name "ESW_TXVN_A_P3") (class "Default")
      (node (ref "T2") (pin "11") (pinfunction "1_TD4+_11") (pintype "bidirectional"))
    )
    (net (code "61") (name "ESW_TXVN_A_P4") (class "Default")
      (node (ref "T1") (pin "23") (pinfunction "2_TD8+_23") (pintype "bidirectional"))
    )
    (net (code "62") (name "ESW_TXVN_A_P5") (class "Default")
      (node (ref "T1") (pin "11") (pinfunction "1_TD4+_11") (pintype "bidirectional"))
    )
    (net (code "63") (name "ESW_TXVN_B_P0") (class "Default")
      (node (ref "R68") (pin "1") (pinfunction "1_1") (pintype "passive"))
      (node (ref "T3") (pin "20") (pinfunction "2_TD7+_20") (pintype "bidirectional"))
    )
    (net (code "64") (name "ESW_TXVN_B_P1") (class "Default")
      (node (ref "T3") (pin "8") (pinfunction "1_TD3+_8") (pintype "bidirectional"))
    )
    (net (code "65") (name "ESW_TXVN_B_P2") (class "Default")
      (node (ref "T2") (pin "20") (pinfunction "2_TD7+_20") (pintype "bidirectional"))
    )
    (net (code "66") (name "ESW_TXVN_B_P3") (class "Default")
      (node (ref "T2") (pin "8") (pinfunction "1_TD3+_8") (pintype "bidirectional"))
    )
    (net (code "67") (name "ESW_TXVN_B_P4") (class "Default")
      (node (ref "T1") (pin "20") (pinfunction "2_TD7+_20") (pintype "bidirectional"))
    )
    (net (code "68") (name "ESW_TXVN_B_P5") (class "Default")
      (node (ref "T1") (pin "8") (pinfunction "1_TD3+_8") (pintype "bidirectional"))
    )
    (net (code "69") (name "ESW_TXVN_C_P0") (class "Default")
      (node (ref "R66") (pin "1") (pinfunction "1_1") (pintype "passive"))
      (node (ref "T3") (pin "17") (pinfunction "2_TD6+_17") (pintype "bidirectional"))
    )
    (net (code "70") (name "ESW_TXVN_C_P1") (class "Default")
      (node (ref "T3") (pin "5") (pinfunction "1_TD2+_5") (pintype "bidirectional"))
    )
    (net (code "71") (name "ESW_TXVN_C_P2") (class "Default")
      (node (ref "T2") (pin "17") (pinfunction "2_TD6+_17") (pintype "bidirectional"))
    )
    (net (code "72") (name "ESW_TXVN_C_P3") (class "Default")
      (node (ref "T2") (pin "5") (pinfunction "1_TD2+_5") (pintype "bidirectional"))
    )
    (net (code "73") (name "ESW_TXVN_C_P4") (class "Default")
      (node (ref "T1") (pin "17") (pinfunction "2_TD6+_17") (pintype "bidirectional"))
    )
    (net (code "74") (name "ESW_TXVN_C_P5") (class "Default")
      (node (ref "T1") (pin "5") (pinfunction "1_TD2+_5") (pintype "bidirectional"))
    )
    (net (code "75") (name "ESW_TXVN_D_P0") (class "Default")
      (node (ref "R64") (pin "1") (pinfunction "1_1") (pintype "passive"))
      (node (ref "T3") (pin "14") (pinfunction "2_TD5+_14") (pintype "bidirectional"))
    )
    (net (code "76") (name "ESW_TXVN_D_P1") (class "Default")
      (node (ref "T3") (pin "2") (pinfunction "1_TD1+_2") (pintype "bidirectional"))
    )
    (net (code "77") (name "ESW_TXVN_D_P2") (class "Default")
      (node (ref "T2") (pin "14") (pinfunction "2_TD5+_14") (pintype "bidirectional"))
    )
    (net (code "78") (name "ESW_TXVN_D_P3") (class "Default")
      (node (ref "T2") (pin "2") (pinfunction "1_TD1+_2") (pintype "bidirectional"))
    )
    (net (code "79") (name "ESW_TXVN_D_P4") (class "Default")
      (node (ref "T1") (pin "14") (pinfunction "2_TD5+_14") (pintype "bidirectional"))
    )
    (net (code "80") (name "ESW_TXVN_D_P5") (class "Default")
      (node (ref "T1") (pin "2") (pinfunction "1_TD1+_2") (pintype "bidirectional"))
    )
    (net (code "81") (name "ESW_TXVP_A_P0") (class "Default")
      (node (ref "R71") (pin "2") (pinfunction "2_2") (pintype "passive"))
      (node (ref "T3") (pin "24") (pinfunction "2_TD8-_24") (pintype "bidirectional"))
    )
    (net (code "82") (name "ESW_TXVP_A_P1") (class "Default")
      (node (ref "T3") (pin "12") (pinfunction "1_TD4-_12") (pintype "bidirectional"))
    )
    (net (code "83") (name "ESW_TXVP_A_P2") (class "Default")
      (node (ref "T2") (pin "24") (pinfunction "2_TD8-_24") (pintype "bidirectional"))
    )
    (net (code "84") (name "ESW_TXVP_A_P3") (class "Default")
      (node (ref "T2") (pin "12") (pinfunction "1_TD4-_12") (pintype "bidirectional"))
    )
    (net (code "85") (name "ESW_TXVP_A_P4") (class "Default")
      (node (ref "T1") (pin "24") (pinfunction "2_TD8-_24") (pintype "bidirectional"))
    )
    (net (code "86") (name "ESW_TXVP_A_P5") (class "Default")
      (node (ref "T1") (pin "12") (pinfunction "1_TD4-_12") (pintype "bidirectional"))
    )
    (net (code "87") (name "ESW_TXVP_B_P0") (class "Default")
      (node (ref "R69") (pin "2") (pinfunction "2_2") (pintype "passive"))
      (node (ref "T3") (pin "21") (pinfunction "2_TD7-_21") (pintype "bidirectional"))
    )
    (net (code "88") (name "ESW_TXVP_B_P1") (class "Default")
      (node (ref "T3") (pin "9") (pinfunction "1_TD3-_9") (pintype "bidirectional"))
    )
    (net (code "89") (name "ESW_TXVP_B_P2") (class "Default")
      (node (ref "T2") (pin "21") (pinfunction "2_TD7-_21") (pintype "bidirectional"))
    )
    (net (code "90") (name "ESW_TXVP_B_P3") (class "Default")
      (node (ref "T2") (pin "9") (pinfunction "1_TD3-_9") (pintype "bidirectional"))
    )
    (net (code "91") (name "ESW_TXVP_B_P4") (class "Default")
      (node (ref "T1") (pin "21") (pinfunction "2_TD7-_21") (pintype "bidirectional"))
    )
    (net (code "92") (name "ESW_TXVP_B_P5") (class "Default")
      (node (ref "T1") (pin "9") (pinfunction "1_TD3-_9") (pintype "bidirectional"))
    )
    (net (code "93") (name "ESW_TXVP_C_P0") (class "Default")
      (node (ref "R67") (pin "2") (pinfunction "2_2") (pintype "passive"))
      (node (ref "T3") (pin "18") (pinfunction "2_TD6-_18") (pintype "bidirectional"))
    )
    (net (code "94") (name "ESW_TXVP_C_P1") (class "Default")
      (node (ref "T3") (pin "6") (pinfunction "1_TD2-_6") (pintype "bidirectional"))
    )
    (net (code "95") (name "ESW_TXVP_C_P2") (class "Default")
      (node (ref "T2") (pin "18") (pinfunction "2_TD6-_18") (pintype "bidirectional"))
    )
    (net (code "96") (name "ESW_TXVP_C_P3") (class "Default")
      (node (ref "T2") (pin "6") (pinfunction "1_TD2-_6") (pintype "bidirectional"))
    )
    (net (code "97") (name "ESW_TXVP_C_P4") (class "Default")
      (node (ref "T1") (pin "18") (pinfunction "2_TD6-_18") (pintype "bidirectional"))
    )
    (net (code "98") (name "ESW_TXVP_C_P5") (class "Default")
      (node (ref "T1") (pin "6") (pinfunction "1_TD2-_6") (pintype "bidirectional"))
    )
    (net (code "99") (name "ESW_TXVP_D_P0") (class "Default")
      (node (ref "R65") (pin "2") (pinfunction "2_2") (pintype "passive"))
      (node (ref "T3") (pin "15") (pinfunction "2_TD5-_15") (pintype "bidirectional"))
    )
    (net (code "100") (name "ESW_TXVP_D_P1") (class "Default")
      (node (ref "T3") (pin "3") (pinfunction "1_TD1-_3") (pintype "bidirectional"))
    )
    (net (code "101") (name "ESW_TXVP_D_P2") (class "Default")
      (node (ref "T2") (pin "15") (pinfunction "2_TD5-_15") (pintype "bidirectional"))
    )
    (net (code "102") (name "ESW_TXVP_D_P3") (class "Default")
      (node (ref "T2") (pin "3") (pinfunction "1_TD1-_3") (pintype "bidirectional"))
    )
    (net (code "103") (name "ESW_TXVP_D_P4") (class "Default")
      (node (ref "T1") (pin "15") (pinfunction "2_TD5-_15") (pintype "bidirectional"))
    )
    (net (code "104") (name "ESW_TXVP_D_P5") (class "Default")
      (node (ref "T1") (pin "3") (pinfunction "1_TD1-_3") (pintype "bidirectional"))
    )
    (net (code "105") (name "GND") (class "Default")
      (node (ref "C11") (pin "1") (pinfunction "1_1") (pintype "passive"))
      (node (ref "C12") (pin "1") (pinfunction "1_1") (pintype "passive"))
      (node (ref "C13") (pin "2") (pinfunction "2_2") (pintype "passive"))
      (node (ref "C14") (pin "1") (pinfunction "1_1") (pintype "passive"))
      (node (ref "C16") (pin "2") (pinfunction "2_2") (pintype "passive"))
      (node (ref "C17") (pin "2") (pinfunction "2_2") (pintype "passive"))
      (node (ref "C20") (pin "2") (pinfunction "2_2") (pintype "passive"))
      (node (ref "C21") (pin "2") (pinfunction "2_2") (pintype "passive"))
      (node (ref "C22") (pin "2") (pinfunction "2_2") (pintype "passive"))
      (node (ref "C34") (pin "2") (pinfunction "2_2") (pintype "passive"))
      (node (ref "C35") (pin "1") (pinfunction "1_1") (pintype "passive"))
      (node (ref "C36") (pin "1") (pinfunction "1_1") (pintype "passive"))
      (node (ref "C37") (pin "1") (pinfunction "1_1") (pintype "passive"))
      (node (ref "C38") (pin "1") (pinfunction "1_1") (pintype "passive"))
      (node (ref "C39") (pin "1") (pinfunction "1_1") (pintype "passive"))
      (node (ref "C40") (pin "1") (pinfunction "1_1") (pintype "passive"))
      (node (ref "C41") (pin "1") (pinfunction "1_1") (pintype "passive"))
      (node (ref "C42") (pin "1") (pinfunction "1_1") (pintype "passive"))
      (node (ref "C43") (pin "1") (pinfunction "1_1") (pintype "passive"))
      (node (ref "C44") (pin "1") (pinfunction "1_1") (pintype "passive"))
      (node (ref "C45") (pin "1") (pinfunction "1_1") (pintype "passive"))
      (node (ref "C46") (pin "1") (pinfunction "1_1") (pintype "passive"))
      (node (ref "C47") (pin "1") (pinfunction "1_1") (pintype "passive"))
      (node (ref "C48") (pin "1") (pinfunction "1_1") (pintype "passive"))
      (node (ref "C49") (pin "1") (pinfunction "1_1") (pintype "passive"))
      (node (ref "C50") (pin "1") (pinfunction "1_1") (pintype "passive"))
      (node (ref "C51") (pin "1") (pinfunction "1_1") (pintype "passive"))
      (node (ref "C52") (pin "1") (pinfunction "1_1") (pintype "passive"))
      (node (ref "C53") (pin "1") (pinfunction "1_1") (pintype "passive"))
      (node (ref "C54") (pin "1") (pinfunction "1_1") (pintype "passive"))
      (node (ref "C55") (pin "1") (pinfunction "1_1") (pintype "passive"))
      (node (ref "C56") (pin "1") (pinfunction "1_1") (pintype "passive"))
      (node (ref "C57") (pin "1") (pinfunction "1_1") (pintype "passive"))
      (node (ref "C58") (pin "1") (pinfunction "1_1") (pintype "passive"))
      (node (ref "C59") (pin "1") (pinfunction "1_1") (pintype "passive"))
      (node (ref "C60") (pin "2") (pinfunction "2_2") (pintype "passive"))
      (node (ref "C7") (pin "1") (pinfunction "1_1") (pintype "passive"))
      (node (ref "JP8") (pin "2") (pinfunction "2_2") (pintype "passive"))
      (node (ref "JP9") (pin "2") (pinfunction "2_2") (pintype "passive"))
      (node (ref "LED3") (pin "2") (pinfunction "K_2") (pintype "passive"))
      (node (ref "R27") (pin "1") (pinfunction "1_1") (pintype "passive"))
      (node (ref "R28") (pin "1") (pinfunction "1_1") (pintype "passive"))
      (node (ref "R44") (pin "1") (pinfunction "1_1") (pintype "passive"))
      (node (ref "U2") (pin "3") (pinfunction "GND_3") (pintype "passive"))
      (node (ref "USB1") (pin "1") (pinfunction "SHELL_1") (pintype "passive"))
      (node (ref "USB1") (pin "2") (pinfunction "SHELL_2") (pintype "passive"))
      (node (ref "USB1") (pin "3") (pinfunction "SHELL_3") (pintype "passive"))
      (node (ref "USB1") (pin "4") (pinfunction "SHELL_4") (pintype "passive"))
      (node (ref "USB1") (pin "A1B12") (pinfunction "GND_A1B12") (pintype "passive"))
      (node (ref "USB1") (pin "B1A12") (pinfunction "GND_B1A12") (pintype "passive"))
      (node (ref "V1") (pin "1") (pinfunction "GND_1") (pintype "passive"))
    )
    (net (code "106") (name "GND_EARTH") (class "Default")
      (node (ref "C40") (pin "2") (pinfunction "2_2") (pintype "passive"))
      (node (ref "R44") (pin "2") (pinfunction "2_2") (pintype "passive"))
      (node (ref "RJ1") (pin "0") (pinfunction "Case1_0") (pintype "passive"))
      (node (ref "RJ2") (pin "0") (pinfunction "Case1_0") (pintype "passive"))
      (node (ref "RJ3") (pin "EH") (pinfunction "EH_EH") (pintype "passive"))
    )
    (net (code "107") (name "Net-(C17-Pad1)") (class "Default")
      (node (ref "C17") (pin "1") (pinfunction "1_1") (pintype "passive"))
      (node (ref "R64") (pin "2") (pinfunction "2_2") (pintype "passive"))
      (node (ref "R65") (pin "1") (pinfunction "1_1") (pintype "passive"))
    )
    (net (code "108") (name "Net-(C20-Pad1)") (class "Default")
      (node (ref "C20") (pin "1") (pinfunction "1_1") (pintype "passive"))
      (node (ref "R66") (pin "2") (pinfunction "2_2") (pintype "passive"))
      (node (ref "R67") (pin "1") (pinfunction "1_1") (pintype "passive"))
    )
    (net (code "109") (name "Net-(C21-Pad1)") (class "Default")
      (node (ref "C21") (pin "1") (pinfunction "1_1") (pintype "passive"))
      (node (ref "R68") (pin "2") (pinfunction "2_2") (pintype "passive"))
      (node (ref "R69") (pin "1") (pinfunction "1_1") (pintype "passive"))
    )
    (net (code "110") (name "Net-(C22-Pad1)") (class "Default")
      (node (ref "C22") (pin "1") (pinfunction "1_1") (pintype "passive"))
      (node (ref "R70") (pin "2") (pinfunction "2_2") (pintype "passive"))
      (node (ref "R71") (pin "1") (pinfunction "1_1") (pintype "passive"))
    )
    (net (code "111") (name "Net-(C34-Pad1)") (class "Default")
      (node (ref "C34") (pin "1") (pinfunction "1_1") (pintype "passive"))
      (node (ref "C60") (pin "1") (pinfunction "1_1") (pintype "passive"))
      (node (ref "R38") (pin "1") (pinfunction "1_1") (pintype "passive"))
      (node (ref "R39") (pin "1") (pinfunction "1_1") (pintype "passive"))
      (node (ref "R40") (pin "1") (pinfunction "1_1") (pintype "passive"))
      (node (ref "R41") (pin "1") (pinfunction "1_1") (pintype "passive"))
      (node (ref "R42") (pin "1") (pinfunction "1_1") (pintype "passive"))
      (node (ref "R43") (pin "1") (pinfunction "1_1") (pintype "passive"))
      (node (ref "R45") (pin "1") (pinfunction "1_1") (pintype "passive"))
      (node (ref "R46") (pin "1") (pinfunction "1_1") (pintype "passive"))
      (node (ref "R47") (pin "1") (pinfunction "1_1") (pintype "passive"))
      (node (ref "R48") (pin "1") (pinfunction "1_1") (pintype "passive"))
      (node (ref "R49") (pin "1") (pinfunction "1_1") (pintype "passive"))
      (node (ref "R50") (pin "1") (pinfunction "1_1") (pintype "passive"))
      (node (ref "R51") (pin "1") (pinfunction "1_1") (pintype "passive"))
      (node (ref "R52") (pin "1") (pinfunction "1_1") (pintype "passive"))
      (node (ref "R53") (pin "1") (pinfunction "1_1") (pintype "passive"))
      (node (ref "R54") (pin "1") (pinfunction "1_1") (pintype "passive"))
      (node (ref "R55") (pin "1") (pinfunction "1_1") (pintype "passive"))
      (node (ref "R56") (pin "1") (pinfunction "1_1") (pintype "passive"))
      (node (ref "R57") (pin "1") (pinfunction "1_1") (pintype "passive"))
      (node (ref "R58") (pin "1") (pinfunction "1_1") (pintype "passive"))
      (node (ref "R59") (pin "1") (pinfunction "1_1") (pintype "passive"))
      (node (ref "R60") (pin "1") (pinfunction "1_1") (pintype "passive"))
      (node (ref "R61") (pin "1") (pinfunction "1_1") (pintype "passive"))
      (node (ref "R62") (pin "1") (pinfunction "1_1") (pintype "passive"))
    )
    (net (code "112") (name "Net-(LED3-A)") (class "Default")
      (node (ref "LED3") (pin "1") (pinfunction "A_1") (pintype "passive"))
      (node (ref "R98") (pin "1") (pinfunction "1_1") (pintype "passive"))
    )
    (net (code "113") (name "Net-(T1-1_MCT1)") (class "Default")
      (node (ref "R38") (pin "2") (pinfunction "2_2") (pintype "passive"))
      (node (ref "T1") (pin "48") (pinfunction "1_MCT1_48") (pintype "input"))
    )
    (net (code "114") (name "Net-(T1-1_MCT2)") (class "Default")
      (node (ref "R39") (pin "2") (pinfunction "2_2") (pintype "passive"))
      (node (ref "T1") (pin "45") (pinfunction "1_MCT2_45") (pintype "input"))
    )
    (net (code "115") (name "Net-(T1-1_MCT3)") (class "Default")
      (node (ref "R40") (pin "2") (pinfunction "2_2") (pintype "passive"))
      (node (ref "T1") (pin "42") (pinfunction "1_MCT3_42") (pintype "input"))
    )
    (net (code "116") (name "Net-(T1-1_MCT4)") (class "Default")
      (node (ref "R41") (pin "2") (pinfunction "2_2") (pintype "passive"))
      (node (ref "T1") (pin "39") (pinfunction "1_MCT4_39") (pintype "input"))
    )
    (net (code "117") (name "Net-(T1-1_TCT1)") (class "Default")
      (node (ref "C35") (pin "2") (pinfunction "2_2") (pintype "passive"))
      (node (ref "T1") (pin "1") (pinfunction "1_TCT1_1") (pintype "input"))
    )
    (net (code "118") (name "Net-(T1-1_TCT2)") (class "Default")
      (node (ref "C36") (pin "2") (pinfunction "2_2") (pintype "passive"))
      (node (ref "T1") (pin "4") (pinfunction "1_TCT2_4") (pintype "input"))
    )
    (net (code "119") (name "Net-(T1-1_TCT3)") (class "Default")
      (node (ref "C37") (pin "2") (pinfunction "2_2") (pintype "passive"))
      (node (ref "T1") (pin "7") (pinfunction "1_TCT3_7") (pintype "input"))
    )
    (net (code "120") (name "Net-(T1-1_TCT4)") (class "Default")
      (node (ref "C38") (pin "2") (pinfunction "2_2") (pintype "passive"))
      (node (ref "T1") (pin "10") (pinfunction "1_TCT4_10") (pintype "input"))
    )
    (net (code "121") (name "Net-(T1-2_MCT5)") (class "Default")
      (node (ref "R42") (pin "2") (pinfunction "2_2") (pintype "passive"))
      (node (ref "T1") (pin "36") (pinfunction "2_MCT5_36") (pintype "input"))
    )
    (net (code "122") (name "Net-(T1-2_MCT6)") (class "Default")
      (node (ref "R43") (pin "2") (pinfunction "2_2") (pintype "passive"))
      (node (ref "T1") (pin "33") (pinfunction "2_MCT6_33") (pintype "input"))
    )
    (net (code "123") (name "Net-(T1-2_MCT7)") (class "Default")
      (node (ref "R45") (pin "2") (pinfunction "2_2") (pintype "passive"))
      (node (ref "T1") (pin "30") (pinfunction "2_MCT7_30") (pintype "input"))
    )
    (net (code "124") (name "Net-(T1-2_MCT8)") (class "Default")
      (node (ref "R46") (pin "2") (pinfunction "2_2") (pintype "passive"))
      (node (ref "T1") (pin "27") (pinfunction "2_MCT8_27") (pintype "input"))
    )
    (net (code "125") (name "Net-(T1-2_TCT5)") (class "Default")
      (node (ref "C39") (pin "2") (pinfunction "2_2") (pintype "passive"))
      (node (ref "T1") (pin "13") (pinfunction "2_TCT5_13") (pintype "input"))
    )
    (net (code "126") (name "Net-(T1-2_TCT6)") (class "Default")
      (node (ref "C41") (pin "2") (pinfunction "2_2") (pintype "passive"))
      (node (ref "T1") (pin "16") (pinfunction "2_TCT6_16") (pintype "input"))
    )
    (net (code "127") (name "Net-(T1-2_TCT7)") (class "Default")
      (node (ref "C42") (pin "2") (pinfunction "2_2") (pintype "passive"))
      (node (ref "T1") (pin "19") (pinfunction "2_TCT7_19") (pintype "input"))
    )
    (net (code "128") (name "Net-(T1-2_TCT8)") (class "Default")
      (node (ref "C43") (pin "2") (pinfunction "2_2") (pintype "passive"))
      (node (ref "T1") (pin "22") (pinfunction "2_TCT8_22") (pintype "input"))
    )
    (net (code "129") (name "Net-(T2-1_MCT1)") (class "Default")
      (node (ref "R47") (pin "2") (pinfunction "2_2") (pintype "passive"))
      (node (ref "T2") (pin "48") (pinfunction "1_MCT1_48") (pintype "input"))
    )
    (net (code "130") (name "Net-(T2-1_MCT2)") (class "Default")
      (node (ref "R48") (pin "2") (pinfunction "2_2") (pintype "passive"))
      (node (ref "T2") (pin "45") (pinfunction "1_MCT2_45") (pintype "input"))
    )
    (net (code "131") (name "Net-(T2-1_MCT3)") (class "Default")
      (node (ref "R49") (pin "2") (pinfunction "2_2") (pintype "passive"))
      (node (ref "T2") (pin "42") (pinfunction "1_MCT3_42") (pintype "input"))
    )
    (net (code "132") (name "Net-(T2-1_MCT4)") (class "Default")
      (node (ref "R50") (pin "2") (pinfunction "2_2") (pintype "passive"))
      (node (ref "T2") (pin "39") (pinfunction "1_MCT4_39") (pintype "input"))
    )
    (net (code "133") (name "Net-(T2-1_TCT1)") (class "Default")
      (node (ref "C44") (pin "2") (pinfunction "2_2") (pintype "passive"))
      (node (ref "T2") (pin "1") (pinfunction "1_TCT1_1") (pintype "input"))
    )
    (net (code "134") (name "Net-(T2-1_TCT2)") (class "Default")
      (node (ref "C45") (pin "2") (pinfunction "2_2") (pintype "passive"))
      (node (ref "T2") (pin "4") (pinfunction "1_TCT2_4") (pintype "input"))
    )
    (net (code "135") (name "Net-(T2-1_TCT3)") (class "Default")
      (node (ref "C46") (pin "2") (pinfunction "2_2") (pintype "passive"))
      (node (ref "T2") (pin "7") (pinfunction "1_TCT3_7") (pintype "input"))
    )
    (net (code "136") (name "Net-(T2-1_TCT4)") (class "Default")
      (node (ref "C47") (pin "2") (pinfunction "2_2") (pintype "passive"))
      (node (ref "T2") (pin "10") (pinfunction "1_TCT4_10") (pintype "input"))
    )
    (net (code "137") (name "Net-(T2-2_MCT5)") (class "Default")
      (node (ref "R51") (pin "2") (pinfunction "2_2") (pintype "passive"))
      (node (ref "T2") (pin "36") (pinfunction "2_MCT5_36") (pintype "input"))
    )
    (net (code "138") (name "Net-(T2-2_MCT6)") (class "Default")
      (node (ref "R52") (pin "2") (pinfunction "2_2") (pintype "passive"))
      (node (ref "T2") (pin "33") (pinfunction "2_MCT6_33") (pintype "input"))
    )
    (net (code "139") (name "Net-(T2-2_MCT7)") (class "Default")
      (node (ref "R53") (pin "2") (pinfunction "2_2") (pintype "passive"))
      (node (ref "T2") (pin "30") (pinfunction "2_MCT7_30") (pintype "input"))
    )
    (net (code "140") (name "Net-(T2-2_MCT8)") (class "Default")
      (node (ref "R54") (pin "2") (pinfunction "2_2") (pintype "passive"))
      (node (ref "T2") (pin "27") (pinfunction "2_MCT8_27") (pintype "input"))
    )
    (net (code "141") (name "Net-(T2-2_TCT5)") (class "Default")
      (node (ref "C48") (pin "2") (pinfunction "2_2") (pintype "passive"))
      (node (ref "T2") (pin "13") (pinfunction "2_TCT5_13") (pintype "input"))
    )
    (net (code "142") (name "Net-(T2-2_TCT6)") (class "Default")
      (node (ref "C49") (pin "2") (pinfunction "2_2") (pintype "passive"))
      (node (ref "T2") (pin "16") (pinfunction "2_TCT6_16") (pintype "input"))
    )
    (net (code "143") (name "Net-(T2-2_TCT7)") (class "Default")
      (node (ref "C50") (pin "2") (pinfunction "2_2") (pintype "passive"))
      (node (ref "T2") (pin "19") (pinfunction "2_TCT7_19") (pintype "input"))
    )
    (net (code "144") (name "Net-(T2-2_TCT8)") (class "Default")
      (node (ref "C51") (pin "2") (pinfunction "2_2") (pintype "passive"))
      (node (ref "T2") (pin "22") (pinfunction "2_TCT8_22") (pintype "input"))
    )
    (net (code "145") (name "Net-(T3-1_MCT1)") (class "Default")
      (node (ref "R55") (pin "2") (pinfunction "2_2") (pintype "passive"))
      (node (ref "T3") (pin "48") (pinfunction "1_MCT1_48") (pintype "input"))
    )
    (net (code "146") (name "Net-(T3-1_MCT2)") (class "Default")
      (node (ref "R56") (pin "2") (pinfunction "2_2") (pintype "passive"))
      (node (ref "T3") (pin "45") (pinfunction "1_MCT2_45") (pintype "input"))
    )
    (net (code "147") (name "Net-(T3-1_MCT3)") (class "Default")
      (node (ref "R57") (pin "2") (pinfunction "2_2") (pintype "passive"))
      (node (ref "T3") (pin "42") (pinfunction "1_MCT3_42") (pintype "input"))
    )
    (net (code "148") (name "Net-(T3-1_MCT4)") (class "Default")
      (node (ref "R58") (pin "2") (pinfunction "2_2") (pintype "passive"))
      (node (ref "T3") (pin "39") (pinfunction "1_MCT4_39") (pintype "input"))
    )
    (net (code "149") (name "Net-(T3-1_TCT1)") (class "Default")
      (node (ref "C52") (pin "2") (pinfunction "2_2") (pintype "passive"))
      (node (ref "T3") (pin "1") (pinfunction "1_TCT1_1") (pintype "input"))
    )
    (net (code "150") (name "Net-(T3-1_TCT2)") (class "Default")
      (node (ref "C53") (pin "2") (pinfunction "2_2") (pintype "passive"))
      (node (ref "T3") (pin "4") (pinfunction "1_TCT2_4") (pintype "input"))
    )
    (net (code "151") (name "Net-(T3-1_TCT3)") (class "Default")
      (node (ref "C54") (pin "2") (pinfunction "2_2") (pintype "passive"))
      (node (ref "T3") (pin "7") (pinfunction "1_TCT3_7") (pintype "input"))
    )
    (net (code "152") (name "Net-(T3-1_TCT4)") (class "Default")
      (node (ref "C55") (pin "2") (pinfunction "2_2") (pintype "passive"))
      (node (ref "T3") (pin "10") (pinfunction "1_TCT4_10") (pintype "input"))
    )
    (net (code "153") (name "Net-(T3-2_MCT5)") (class "Default")
      (node (ref "R59") (pin "2") (pinfunction "2_2") (pintype "passive"))
      (node (ref "T3") (pin "36") (pinfunction "2_MCT5_36") (pintype "input"))
    )
    (net (code "154") (name "Net-(T3-2_MCT6)") (class "Default")
      (node (ref "R60") (pin "2") (pinfunction "2_2") (pintype "passive"))
      (node (ref "T3") (pin "33") (pinfunction "2_MCT6_33") (pintype "input"))
    )
    (net (code "155") (name "Net-(T3-2_MCT7)") (class "Default")
      (node (ref "R61") (pin "2") (pinfunction "2_2") (pintype "passive"))
      (node (ref "T3") (pin "30") (pinfunction "2_MCT7_30") (pintype "input"))
    )
    (net (code "156") (name "Net-(T3-2_MCT8)") (class "Default")
      (node (ref "R62") (pin "2") (pinfunction "2_2") (pintype "passive"))
      (node (ref "T3") (pin "27") (pinfunction "2_MCT8_27") (pintype "input"))
    )
    (net (code "157") (name "Net-(USB1-CC1)") (class "Default")
      (node (ref "R27") (pin "2") (pinfunction "2_2") (pintype "passive"))
      (node (ref "USB1") (pin "A5") (pinfunction "CC1_A5") (pintype "passive"))
    )
    (net (code "158") (name "Net-(USB1-CC2)") (class "Default")
      (node (ref "R28") (pin "2") (pinfunction "2_2") (pintype "passive"))
      (node (ref "USB1") (pin "B5") (pinfunction "CC2_B5") (pintype "passive"))
    )
    (net (code "159") (name "UART0_RXD") (class "Default")
      (node (ref "R33") (pin "1") (pinfunction "1_1") (pintype "passive"))
    )
    (net (code "160") (name "UART0_TXD") (class "Default")
      (node (ref "R32") (pin "1") (pinfunction "1_1") (pintype "passive"))
    )
    (net (code "161") (name "USB_VBUS") (class "Default")
      (node (ref "R63") (pin "2") (pinfunction "2_2") (pintype "passive"))
    )
    (net (code "162") (name "unconnected-(U2-CTS-Pad5)") (class "Default")
      (node (ref "U2") (pin "5") (pinfunction "CTS_5") (pintype "passive"))
    )
    (net (code "163") (name "unconnected-(U2-RTS-Pad4)") (class "Default")
      (node (ref "U2") (pin "4") (pinfunction "RTS_4") (pintype "passive"))
    )
    (net (code "164") (name "unconnected-(U2-TNOW-Pad6)") (class "Default")
      (node (ref "U2") (pin "6") (pinfunction "TNOW_6") (pintype "passive"))
    )
    (net (code "165") (name "unconnected-(USB1-SBU1-PadA8)") (class "Default")
      (node (ref "USB1") (pin "A8") (pinfunction "SBU1_A8") (pintype "passive"))
    )
    (net (code "166") (name "unconnected-(USB1-SBU2-PadB8)") (class "Default")
      (node (ref "USB1") (pin "B8") (pinfunction "SBU2_B8") (pintype "passive"))
    )
  )
)
